# chareger.net
KiCad netlist of a schematic drawn in EAGLE
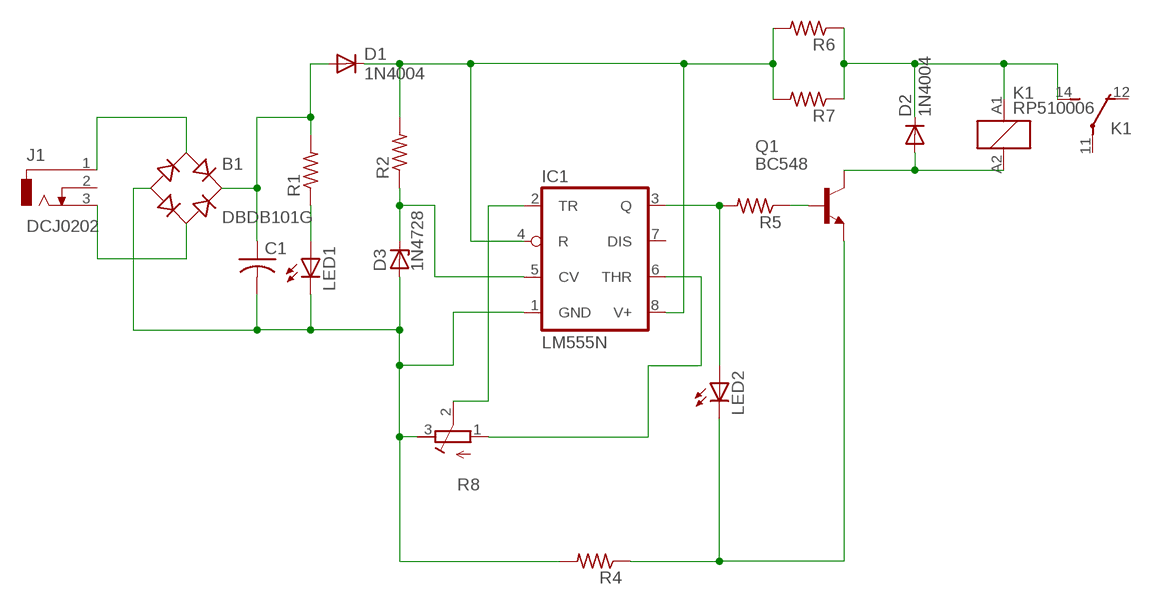
[diagram p0: schematic, sheet 1]

(export (version "E")
  (design (tool "Eeschema 10.0.6"))
  (components
    (comp (ref "B1")
      (value "DBDB101G")
      (footprint "eagle-import:DB")
      (libsource (lib "eagle-import") (part "DB?GDB101"))
    )
    (comp (ref "C1")
      (value "C-US025-050X050")
      (footprint "eagle-import:C025-050X050")
      (libsource (lib "eagle-import") (part "C-US025-050X050"))
    )
    (comp (ref "D1")
      (value "1N4004")
      (footprint "eagle-import:DO41-10")
      (libsource (lib "eagle-import") (part "1N4004"))
    )
    (comp (ref "D2")
      (value "1N4004")
      (footprint "eagle-import:DO41-10")
      (libsource (lib "eagle-import") (part "1N4004"))
    )
    (comp (ref "D3")
      (value "1N4728")
      (footprint "eagle-import:DO41Z10")
      (libsource (lib "eagle-import") (part "1N4728"))
    )
    (comp (ref "IC1")
      (value "LM555N")
      (footprint "eagle-import:DIL08-ROUND")
      (libsource (lib "eagle-import") (part "555NLM"))
    )
    (comp (ref "J1")
      (value "DCJ0202")
      (footprint "eagle-import:DCJ0202")
      (libsource (lib "eagle-import") (part "DCJ0202"))
    )
    (comp (ref "K1")
      (value "RP510006")
      (footprint "eagle-import:RP51")
      (libsource (lib "eagle-import") (part "RP510006"))
    )
    (comp (ref "LED1")
      (value "LEDB152")
      (footprint "eagle-import:Q62902-B152")
      (libsource (lib "eagle-import") (part "LEDB152"))
    )
    (comp (ref "LED2")
      (value "LEDB152")
      (footprint "eagle-import:Q62902-B152")
      (libsource (lib "eagle-import") (part "LEDB152"))
    )
    (comp (ref "Q1")
      (value "BC548")
      (footprint "eagle-import:TO92-EBC")
      (libsource (lib "eagle-import") (part "BC548"))
    )
    (comp (ref "R1")
      (value "R-US_0204/5")
      (footprint "eagle-import:0204_5")
      (libsource (lib "eagle-import") (part "R-US_0204/5"))
    )
    (comp (ref "R2")
      (value "R-US_0204/5")
      (footprint "eagle-import:0204_5")
      (libsource (lib "eagle-import") (part "R-US_0204/5"))
    )
    (comp (ref "R4")
      (value "R-US_0204/5")
      (footprint "eagle-import:0204_5")
      (libsource (lib "eagle-import") (part "R-US_0204/5"))
    )
    (comp (ref "R5")
      (value "R-US_0204/5")
      (footprint "eagle-import:0204_5")
      (libsource (lib "eagle-import") (part "R-US_0204/5"))
    )
    (comp (ref "R6")
      (value "R-US_0204/5")
      (footprint "eagle-import:0204_5")
      (libsource (lib "eagle-import") (part "R-US_0204/5"))
    )
    (comp (ref "R7")
      (value "R-US_0204/5")
      (footprint "eagle-import:0204_5")
      (libsource (lib "eagle-import") (part "R-US_0204/5"))
    )
    (comp (ref "R8")
      (value "R-TRIMM74X")
      (footprint "eagle-import:RTRIM74X")
      (libsource (lib "eagle-import") (part "R-TRIMM74X"))
    )
  )
  (nets
    (net (code "1") (name "Net-(B1-Pad+)") (class "Default")
      (node (ref "B1") (pin "+") (pinfunction "+_+") (pintype "passive"))
      (node (ref "C1") (pin "1") (pinfunction "1_1") (pintype "passive"))
      (node (ref "D1") (pin "A") (pinfunction "A_A") (pintype "passive"))
      (node (ref "R1") (pin "2") (pinfunction "2_2") (pintype "passive"))
    )
    (net (code "2") (name "Net-(B1-PadAC1)") (class "Default")
      (node (ref "B1") (pin "AC1") (pinfunction "AC1_AC1") (pintype "passive"))
      (node (ref "J1") (pin "1") (pinfunction "1_1") (pintype "passive"))
    )
    (net (code "3") (name "Net-(B1-PadAC2)") (class "Default")
      (node (ref "B1") (pin "AC2") (pinfunction "AC2_AC2") (pintype "passive"))
      (node (ref "J1") (pin "3") (pinfunction "3_3") (pintype "passive"))
    )
    (net (code "4") (name "Net-(IC1-CV)") (class "Default")
      (node (ref "D3") (pin "C") (pinfunction "C_C") (pintype "passive"))
      (node (ref "IC1") (pin "5") (pinfunction "CV_5") (pintype "input"))
      (node (ref "R2") (pin "1") (pinfunction "1_1") (pintype "passive"))
    )
    (net (code "5") (name "Net-(IC1-GND)") (class "Default")
      (node (ref "B1") (pin "-") (pinfunction "-_-") (pintype "passive"))
      (node (ref "C1") (pin "2") (pinfunction "2_2") (pintype "passive"))
      (node (ref "D3") (pin "A") (pinfunction "A_A") (pintype "passive"))
      (node (ref "IC1") (pin "1") (pinfunction "GND_1") (pintype "power_in"))
      (node (ref "LED1") (pin "K") (pinfunction "C_K") (pintype "passive"))
      (node (ref "R4") (pin "2") (pinfunction "2_2") (pintype "passive"))
      (node (ref "R8") (pin "3") (pinfunction "E_3") (pintype "passive"))
    )
    (net (code "6") (name "Net-(IC1-Q)") (class "Default")
      (node (ref "IC1") (pin "3") (pinfunction "Q_3") (pintype "output"))
      (node (ref "LED2") (pin "A") (pinfunction "A_A") (pintype "passive"))
      (node (ref "R5") (pin "2") (pinfunction "2_2") (pintype "passive"))
    )
    (net (code "7") (name "Net-(IC1-R)") (class "Default")
      (node (ref "D1") (pin "C") (pinfunction "C_C") (pintype "passive"))
      (node (ref "IC1") (pin "4") (pinfunction "R_4") (pintype "input"))
      (node (ref "IC1") (pin "8") (pinfunction "V+_8") (pintype "power_in"))
      (node (ref "R2") (pin "2") (pinfunction "2_2") (pintype "passive"))
      (node (ref "R6") (pin "2") (pinfunction "2_2") (pintype "passive"))
      (node (ref "R7") (pin "2") (pinfunction "2_2") (pintype "passive"))
    )
    (net (code "8") (name "Net-(IC1-THR)") (class "Default")
      (node (ref "IC1") (pin "6") (pinfunction "THR_6") (pintype "input"))
      (node (ref "R8") (pin "1") (pinfunction "A_1") (pintype "passive"))
    )
    (net (code "9") (name "Net-(IC1-TR)") (class "Default")
      (node (ref "IC1") (pin "2") (pinfunction "TR_2") (pintype "input"))
      (node (ref "R8") (pin "2") (pinfunction "S_2") (pintype "passive"))
    )
    (net (code "10") (name "Net-(K1A-1)") (class "Default")
      (node (ref "D2") (pin "C") (pinfunction "C_C") (pintype "passive"))
      (node (ref "K1") (pin "14") (pinfunction "S_14") (pintype "passive"))
      (node (ref "K1") (pin "A1") (pinfunction "1_A1") (pintype "passive"))
      (node (ref "R6") (pin "1") (pinfunction "1_1") (pintype "passive"))
      (node (ref "R7") (pin "1") (pinfunction "1_1") (pintype "passive"))
    )
    (net (code "11") (name "Net-(K1A-2)") (class "Default")
      (node (ref "D2") (pin "A") (pinfunction "A_A") (pintype "passive"))
      (node (ref "K1") (pin "A2") (pinfunction "2_A2") (pintype "passive"))
      (node (ref "Q1") (pin "C") (pinfunction "C_C") (pintype "passive"))
    )
    (net (code "12") (name "Net-(LED1-PadA)") (class "Default")
      (node (ref "LED1") (pin "A") (pinfunction "A_A") (pintype "passive"))
      (node (ref "R1") (pin "1") (pinfunction "1_1") (pintype "passive"))
    )
    (net (code "13") (name "Net-(LED2-C)") (class "Default")
      (node (ref "LED2") (pin "K") (pinfunction "C_K") (pintype "passive"))
      (node (ref "Q1") (pin "E") (pinfunction "E_E") (pintype "passive"))
      (node (ref "R4") (pin "1") (pinfunction "1_1") (pintype "passive"))
    )
    (net (code "14") (name "Net-(Q1-PadB)") (class "Default")
      (node (ref "Q1") (pin "B") (pinfunction "B_B") (pintype "passive"))
      (node (ref "R5") (pin "1") (pinfunction "1_1") (pintype "passive"))
    )
    (net (code "15") (name "unconnected-(IC1-DIS-Pad7)") (class "Default")
      (node (ref "IC1") (pin "7") (pinfunction "DIS_7") (pintype "input"))
    )
    (net (code "16") (name "unconnected-(J1-Pad2)") (class "Default")
      (node (ref "J1") (pin "2") (pinfunction "2_2") (pintype "passive"))
    )
    (net (code "17") (name "unconnected-(K1B-O-Pad12)") (class "Default")
      (node (ref "K1") (pin "12") (pinfunction "O_12") (pintype "passive"))
    )
    (net (code "18") (name "unconnected-(K1B-P-Pad11)") (class "Default")
      (node (ref "K1") (pin "11") (pinfunction "P_11") (pintype "passive"))
    )
  )
)
